# LCD.net
KiCad netlist of a schematic drawn in Altium Designer
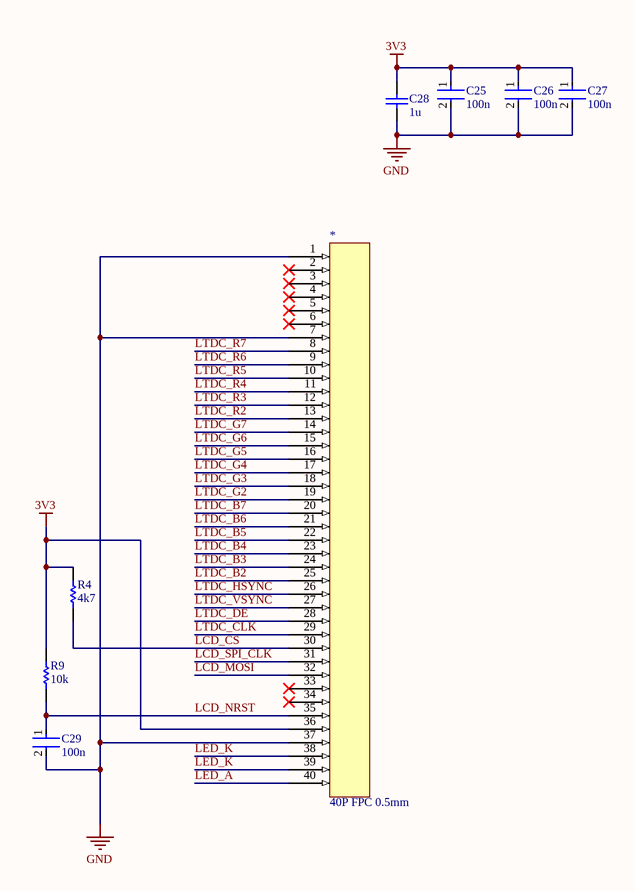
[diagram p0: LCD.SchDoc]

(export (version "E")
  (design (tool "Eeschema 10.0.6"))
  (components
    (comp (ref "*")
      (value "40P FPC 0.5mm")
      (footprint "CONN_62684-402100ALF_AMP")
      (libsource (lib "Master") (part "40P FPC 0.5mm"))
    )
    (comp (ref "C25")
      (value "100n")
      (footprint "FP-GRM188-0_1-e0_2_0_55-IPC_A")
      (description "Chip Multilayer Ceramic Capacitors for General Purpose, 0603, 10uF, X5R, 15%, 20%, 6.3V")
      (fields (field (name "VOLTAGE") "6.3V") (field (name "TOLERANCE") "20%"))
      (libsource (lib "Altium Content Vault") (part "02cd4be3c70576c341d710602a673aa"))
    )
    (comp (ref "C26")
      (value "100n")
      (footprint "FP-GRM188-0_1-e0_2_0_55-IPC_A")
      (description "Chip Multilayer Ceramic Capacitors for General Purpose, 0603, 10uF, X5R, 15%, 20%, 6.3V")
      (fields (field (name "VOLTAGE") "6.3V") (field (name "TOLERANCE") "20%"))
      (libsource (lib "Altium Content Vault") (part "02cd4be3c70576c341d710602a673aa"))
    )
    (comp (ref "C27")
      (value "100n")
      (footprint "FP-GRM188-0_1-e0_2_0_55-IPC_A")
      (description "Chip Multilayer Ceramic Capacitors for General Purpose, 0603, 10uF, X5R, 15%, 20%, 6.3V")
      (fields (field (name "VOLTAGE") "6.3V") (field (name "TOLERANCE") "20%"))
      (libsource (lib "Altium Content Vault") (part "02cd4be3c70576c341d710602a673aa"))
    )
    (comp (ref "C28")
      (value "1u")
      (footprint "CAPC2013X135X45LL10T25")
      (description "Chip Capacitor, 4.7 uF, +/- 10%, 16 V, -55 to 85 degC, 0805 (2012 Metric), RoHS, Tape and Reel")
      (fields (field (name "TOLERANCE") "10%") (field (name "PARTNUMBER") "GRM21BR61C475KA88L"))
      (libsource (lib "Altium Content Vault") (part "CAP-NP-2"))
    )
    (comp (ref "C29")
      (value "100n")
      (footprint "FP-GRM188-0_1-e0_2_0_55-IPC_A")
      (description "Chip Multilayer Ceramic Capacitors for General Purpose, 0603, 10uF, X5R, 15%, 20%, 6.3V")
      (fields (field (name "VOLTAGE") "6.3V") (field (name "TOLERANCE") "20%"))
      (libsource (lib "Altium Content Vault") (part "02cd4be3c70576c341d710602a673aa"))
    )
    (comp (ref "R4")
      (value "4k7")
      (footprint "RESC1608X55X30ML15T15")
      (fields (field (name "PART NUMBER") "ERJ-3EKF1003V") (field (name "MANUFACTURER") "Panasonic"))
      (libsource (lib "Altium Content Vault") (part "RES"))
    )
    (comp (ref "R9")
      (value "10k")
      (footprint "RESC1608X55X30ML15T15")
      (fields (field (name "PART NUMBER") "ERJ-3EKF1003V") (field (name "MANUFACTURER") "Panasonic"))
      (libsource (lib "Altium Content Vault") (part "RES"))
    )
  )
  (nets
    (net (code "1") (name "/LCD_CS") (class "Default")
      (node (ref "*") (pin "30") (pintype "input"))
      (node (ref "R4") (pin "1") (pinfunction "1_1") (pintype "passive"))
    )
    (net (code "2") (name "/LCD_MOSI") (class "Default") (node (ref "*") (pin "32") (pintype "input")))
    (net (code "3") (name "/LCD_NRST") (class "Default")
      (node (ref "*") (pin "35") (pintype "input"))
      (node (ref "C29") (pin "1") (pinfunction "1_1") (pintype "passive"))
      (node (ref "R9") (pin "1") (pinfunction "1_1") (pintype "passive"))
    )
    (net (code "4") (name "/LCD_SPI_CLK") (class "Default") (node (ref "*") (pin "31") (pintype "input")))
    (net (code "5") (name "/LED_A") (class "Default") (node (ref "*") (pin "40") (pintype "input")))
    (net (code "6") (name "/LED_K") (class "Default")
      (node (ref "*") (pin "38") (pintype "input"))
      (node (ref "*") (pin "39") (pintype "input"))
    )
    (net (code "7") (name "/LTDC_B2") (class "Default") (node (ref "*") (pin "25") (pintype "input")))
    (net (code "8") (name "/LTDC_B3") (class "Default") (node (ref "*") (pin "24") (pintype "input")))
    (net (code "9") (name "/LTDC_B4") (class "Default") (node (ref "*") (pin "23") (pintype "input")))
    (net (code "10") (name "/LTDC_B5") (class "Default") (node (ref "*") (pin "22") (pintype "input")))
    (net (code "11") (name "/LTDC_B6") (class "Default") (node (ref "*") (pin "21") (pintype "input")))
    (net (code "12") (name "/LTDC_B7") (class "Default") (node (ref "*") (pin "20") (pintype "input")))
    (net (code "13") (name "/LTDC_CLK") (class "Default") (node (ref "*") (pin "29") (pintype "input")))
    (net (code "14") (name "/LTDC_DE") (class "Default") (node (ref "*") (pin "28") (pintype "input")))
    (net (code "15") (name "/LTDC_G2") (class "Default") (node (ref "*") (pin "19") (pintype "input")))
    (net (code "16") (name "/LTDC_G3") (class "Default") (node (ref "*") (pin "18") (pintype "input")))
    (net (code "17") (name "/LTDC_G4") (class "Default") (node (ref "*") (pin "17") (pintype "input")))
    (net (code "18") (name "/LTDC_G5") (class "Default") (node (ref "*") (pin "16") (pintype "input")))
    (net (code "19") (name "/LTDC_G6") (class "Default") (node (ref "*") (pin "15") (pintype "input")))
    (net (code "20") (name "/LTDC_G7") (class "Default") (node (ref "*") (pin "14") (pintype "input")))
    (net (code "21") (name "/LTDC_HSYNC") (class "Default") (node (ref "*") (pin "26") (pintype "input")))
    (net (code "22") (name "/LTDC_R2") (class "Default") (node (ref "*") (pin "13") (pintype "input")))
    (net (code "23") (name "/LTDC_R3") (class "Default") (node (ref "*") (pin "12") (pintype "input")))
    (net (code "24") (name "/LTDC_R4") (class "Default") (node (ref "*") (pin "11") (pintype "input")))
    (net (code "25") (name "/LTDC_R5") (class "Default") (node (ref "*") (pin "10") (pintype "input")))
    (net (code "26") (name "/LTDC_R6") (class "Default") (node (ref "*") (pin "9") (pintype "input")))
    (net (code "27") (name "/LTDC_R7") (class "Default") (node (ref "*") (pin "8") (pintype "input")))
    (net (code "28") (name "/LTDC_VSYNC") (class "Default") (node (ref "*") (pin "27") (pintype "input")))
    (net (code "29") (name "3V3") (class "Default")
      (node (ref "*") (pin "36") (pintype "input"))
      (node (ref "C25") (pin "1") (pinfunction "1_1") (pintype "passive"))
      (node (ref "C26") (pin "1") (pinfunction "1_1") (pintype "passive"))
      (node (ref "C27") (pin "1") (pinfunction "1_1") (pintype "passive"))
      (node (ref "C28") (pin "2") (pinfunction "2_2") (pintype "passive"))
      (node (ref "R4") (pin "2") (pinfunction "2_2") (pintype "passive"))
      (node (ref "R9") (pin "2") (pinfunction "2_2") (pintype "passive"))
    )
    (net (code "30") (name "GND") (class "Default")
      (node (ref "*") (pin "1") (pintype "input"))
      (node (ref "*") (pin "37") (pintype "input"))
      (node (ref "*") (pin "7") (pintype "input"))
      (node (ref "C25") (pin "2") (pinfunction "2_2") (pintype "passive"))
      (node (ref "C26") (pin "2") (pinfunction "2_2") (pintype "passive"))
      (node (ref "C27") (pin "2") (pinfunction "2_2") (pintype "passive"))
      (node (ref "C28") (pin "1") (pinfunction "1_1") (pintype "passive"))
      (node (ref "C29") (pin "2") (pinfunction "2_2") (pintype "passive"))
    )
    (net (code "31") (name "unconnected-(*-Pad2)") (class "Default")
      (node (ref "*") (pin "2") (pintype "input+no_connect"))
    )
    (net (code "32") (name "unconnected-(*-Pad3)") (class "Default")
      (node (ref "*") (pin "3") (pintype "input+no_connect"))
    )
    (net (code "33") (name "unconnected-(*-Pad4)") (class "Default")
      (node (ref "*") (pin "4") (pintype "input+no_connect"))
    )
    (net (code "34") (name "unconnected-(*-Pad5)") (class "Default")
      (node (ref "*") (pin "5") (pintype "input+no_connect"))
    )
    (net (code "35") (name "unconnected-(*-Pad6)") (class "Default")
      (node (ref "*") (pin "6") (pintype "input+no_connect"))
    )
    (net (code "36") (name "unconnected-(*-Pad33)") (class "Default")
      (node (ref "*") (pin "33") (pintype "input+no_connect"))
    )
    (net (code "37") (name "unconnected-(*-Pad34)") (class "Default")
      (node (ref "*") (pin "34") (pintype "input+no_connect"))
    )
  )
)
